# oscillator_board.net
KiCad netlist of a schematic drawn in EAGLE
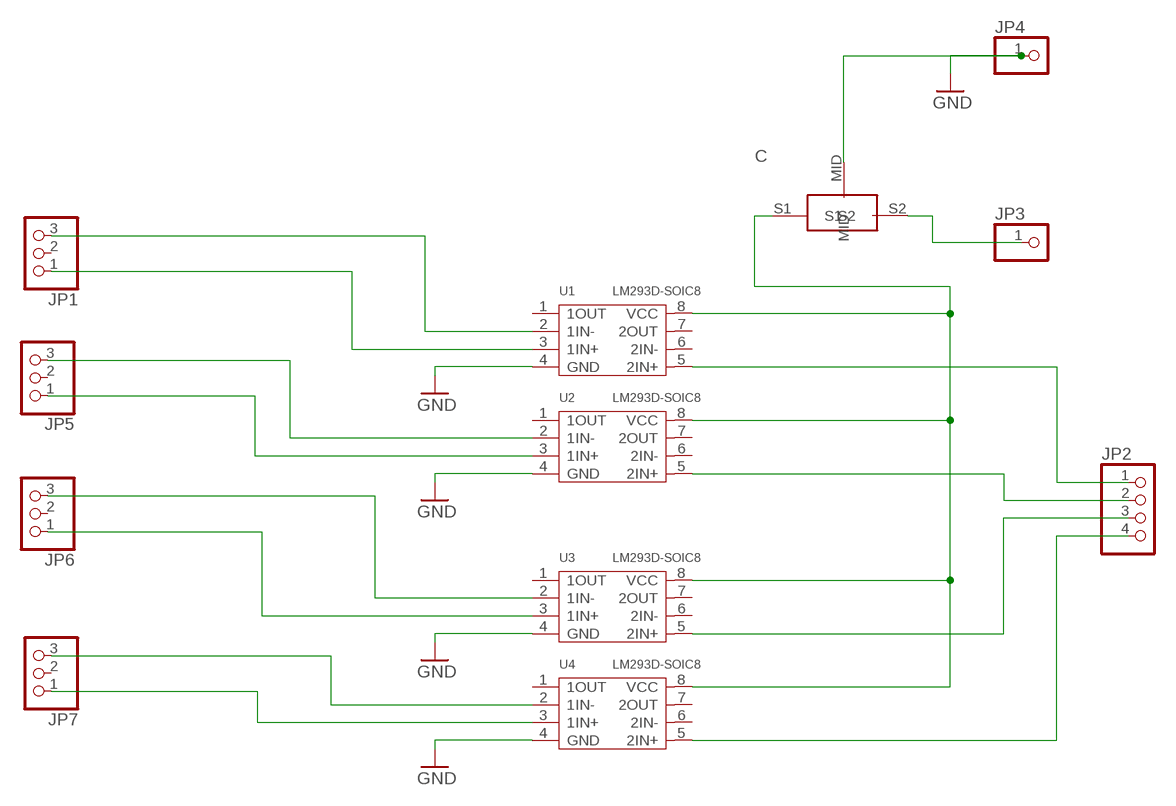
[diagram p0: schematic, sheet 1]

(export (version "E")
  (design (tool "Eeschema 10.0.6"))
  (components
    (comp (ref "JP1")
      (value "PINHD-1X3")
      (footprint "eagle-import:1X03")
      (libsource (lib "eagle-import") (part "PINHD-1X3"))
    )
    (comp (ref "JP2")
      (value "PINHD-1X4")
      (footprint "eagle-import:1X04")
      (libsource (lib "eagle-import") (part "PINHD-1X4"))
    )
    (comp (ref "JP3")
      (value "PINHD-1X1")
      (footprint "eagle-import:1X01")
      (libsource (lib "eagle-import") (part "PINHD-1X1"))
    )
    (comp (ref "JP4")
      (value "PINHD-1X1")
      (footprint "eagle-import:1X01")
      (libsource (lib "eagle-import") (part "PINHD-1X1"))
    )
    (comp (ref "JP5")
      (value "PINHD-1X3")
      (footprint "eagle-import:1X03")
      (libsource (lib "eagle-import") (part "PINHD-1X3"))
    )
    (comp (ref "JP6")
      (value "PINHD-1X3")
      (footprint "eagle-import:1X03")
      (libsource (lib "eagle-import") (part "PINHD-1X3"))
    )
    (comp (ref "JP7")
      (value "PINHD-1X3")
      (footprint "eagle-import:1X03")
      (libsource (lib "eagle-import") (part "PINHD-1X3"))
    )
    (comp (ref "OSCILLATOR1")
      (value "CSMD")
      (footprint "eagle-import:C")
      (libsource (lib "eagle-import") (part "CSMD"))
    )
    (comp (ref "U1")
      (value "LM293D-SOIC8")
      (footprint "eagle-import:SOIC8-1.27-5X4MM")
      (fields (field (name "MPN") "LM293D") (field (name "SPICEPREFIX") "X"))
      (libsource (lib "eagle-import") (part "AMPLIFIER-LM293D(SOIC8)"))
    )
    (comp (ref "U2")
      (value "LM293D-SOIC8")
      (footprint "eagle-import:SOIC8-1.27-5X4MM")
      (fields (field (name "MPN") "LM293D"))
      (libsource (lib "eagle-import") (part "AMPLIFIER-LM293D(SOIC8)"))
    )
    (comp (ref "U3")
      (value "LM293D-SOIC8")
      (footprint "eagle-import:SOIC8-1.27-5X4MM")
      (fields (field (name "MPN") "LM293D"))
      (libsource (lib "eagle-import") (part "AMPLIFIER-LM293D(SOIC8)"))
    )
    (comp (ref "U4")
      (value "LM293D-SOIC8")
      (footprint "eagle-import:SOIC8-1.27-5X4MM")
      (fields (field (name "MPN") "LM293D"))
      (libsource (lib "eagle-import") (part "AMPLIFIER-LM293D(SOIC8)"))
    )
  )
  (nets
    (net (code "1") (name "GND") (class "Default")
      (node (ref "JP4") (pin "1") (pinfunction "1_1") (pintype "passive"))
      (node (ref "OSCILLATOR1") (pin "MID") (pinfunction "MID_MID") (pintype "bidirectional"))
      (node (ref "U1") (pin "4") (pinfunction "GND_4") (pintype "power_in"))
      (node (ref "U2") (pin "4") (pinfunction "GND_4") (pintype "power_in"))
      (node (ref "U3") (pin "4") (pinfunction "GND_4") (pintype "power_in"))
      (node (ref "U4") (pin "4") (pinfunction "GND_4") (pintype "power_in"))
    )
    (net (code "2") (name "Net-(JP3-Pad1)") (class "Default")
      (node (ref "JP3") (pin "1") (pinfunction "1_1") (pintype "passive"))
      (node (ref "OSCILLATOR1") (pin "S2") (pinfunction "S2_S2") (pintype "bidirectional"))
    )
    (net (code "3") (name "Net-(U1-1IN+)") (class "Default")
      (node (ref "JP1") (pin "1") (pinfunction "1_1") (pintype "passive"))
      (node (ref "U1") (pin "3") (pinfunction "1IN+_3") (pintype "input"))
    )
    (net (code "4") (name "Net-(U1-1IN-)") (class "Default")
      (node (ref "JP1") (pin "3") (pinfunction "3_3") (pintype "passive"))
      (node (ref "U1") (pin "2") (pinfunction "1IN-_2") (pintype "input"))
    )
    (net (code "5") (name "Net-(U1-2IN+)") (class "Default")
      (node (ref "JP2") (pin "1") (pinfunction "1_1") (pintype "passive"))
      (node (ref "U1") (pin "5") (pinfunction "2IN+_5") (pintype "input"))
    )
    (net (code "6") (name "Net-(U1-VCC)") (class "Default")
      (node (ref "OSCILLATOR1") (pin "S1") (pinfunction "S1_S1") (pintype "bidirectional"))
      (node (ref "U1") (pin "8") (pinfunction "VCC_8") (pintype "power_in"))
      (node (ref "U2") (pin "8") (pinfunction "VCC_8") (pintype "power_in"))
      (node (ref "U3") (pin "8") (pinfunction "VCC_8") (pintype "power_in"))
      (node (ref "U4") (pin "8") (pinfunction "VCC_8") (pintype "power_in"))
    )
    (net (code "7") (name "Net-(U2-1IN+)") (class "Default")
      (node (ref "JP5") (pin "1") (pinfunction "1_1") (pintype "passive"))
      (node (ref "U2") (pin "3") (pinfunction "1IN+_3") (pintype "input"))
    )
    (net (code "8") (name "Net-(U2-1IN-)") (class "Default")
      (node (ref "JP5") (pin "3") (pinfunction "3_3") (pintype "passive"))
      (node (ref "U2") (pin "2") (pinfunction "1IN-_2") (pintype "input"))
    )
    (net (code "9") (name "Net-(U2-2IN+)") (class "Default")
      (node (ref "JP2") (pin "2") (pinfunction "2_2") (pintype "passive"))
      (node (ref "U2") (pin "5") (pinfunction "2IN+_5") (pintype "input"))
    )
    (net (code "10") (name "Net-(U3-1IN+)") (class "Default")
      (node (ref "JP6") (pin "1") (pinfunction "1_1") (pintype "passive"))
      (node (ref "U3") (pin "3") (pinfunction "1IN+_3") (pintype "input"))
    )
    (net (code "11") (name "Net-(U3-1IN-)") (class "Default")
      (node (ref "JP6") (pin "3") (pinfunction "3_3") (pintype "passive"))
      (node (ref "U3") (pin "2") (pinfunction "1IN-_2") (pintype "input"))
    )
    (net (code "12") (name "Net-(U3-2IN+)") (class "Default")
      (node (ref "JP2") (pin "3") (pinfunction "3_3") (pintype "passive"))
      (node (ref "U3") (pin "5") (pinfunction "2IN+_5") (pintype "input"))
    )
    (net (code "13") (name "Net-(U4-1IN+)") (class "Default")
      (node (ref "JP7") (pin "1") (pinfunction "1_1") (pintype "passive"))
      (node (ref "U4") (pin "3") (pinfunction "1IN+_3") (pintype "input"))
    )
    (net (code "14") (name "Net-(U4-1IN-)") (class "Default")
      (node (ref "JP7") (pin "3") (pinfunction "3_3") (pintype "passive"))
      (node (ref "U4") (pin "2") (pinfunction "1IN-_2") (pintype "input"))
    )
    (net (code "15") (name "Net-(U4-2IN+)") (class "Default")
      (node (ref "JP2") (pin "4") (pinfunction "4_4") (pintype "passive"))
      (node (ref "U4") (pin "5") (pinfunction "2IN+_5") (pintype "input"))
    )
    (net (code "16") (name "unconnected-(JP1-Pad2)") (class "Default")
      (node (ref "JP1") (pin "2") (pinfunction "2_2") (pintype "passive"))
    )
    (net (code "17") (name "unconnected-(JP5-Pad2)") (class "Default")
      (node (ref "JP5") (pin "2") (pinfunction "2_2") (pintype "passive"))
    )
    (net (code "18") (name "unconnected-(JP6-Pad2)") (class "Default")
      (node (ref "JP6") (pin "2") (pinfunction "2_2") (pintype "passive"))
    )
    (net (code "19") (name "unconnected-(JP7-Pad2)") (class "Default")
      (node (ref "JP7") (pin "2") (pinfunction "2_2") (pintype "passive"))
    )
    (net (code "20") (name "unconnected-(U1-1OUT-Pad1)") (class "Default")
      (node (ref "U1") (pin "1") (pinfunction "1OUT_1") (pintype "output"))
    )
    (net (code "21") (name "unconnected-(U1-2IN--Pad6)") (class "Default")
      (node (ref "U1") (pin "6") (pinfunction "2IN-_6") (pintype "input"))
    )
    (net (code "22") (name "unconnected-(U1-2OUT-Pad7)") (class "Default")
      (node (ref "U1") (pin "7") (pinfunction "2OUT_7") (pintype "output"))
    )
    (net (code "23") (name "unconnected-(U2-1OUT-Pad1)") (class "Default")
      (node (ref "U2") (pin "1") (pinfunction "1OUT_1") (pintype "output"))
    )
    (net (code "24") (name "unconnected-(U2-2IN--Pad6)") (class "Default")
      (node (ref "U2") (pin "6") (pinfunction "2IN-_6") (pintype "input"))
    )
    (net (code "25") (name "unconnected-(U2-2OUT-Pad7)") (class "Default")
      (node (ref "U2") (pin "7") (pinfunction "2OUT_7") (pintype "output"))
    )
    (net (code "26") (name "unconnected-(U3-1OUT-Pad1)") (class "Default")
      (node (ref "U3") (pin "1") (pinfunction "1OUT_1") (pintype "output"))
    )
    (net (code "27") (name "unconnected-(U3-2IN--Pad6)") (class "Default")
      (node (ref "U3") (pin "6") (pinfunction "2IN-_6") (pintype "input"))
    )
    (net (code "28") (name "unconnected-(U3-2OUT-Pad7)") (class "Default")
      (node (ref "U3") (pin "7") (pinfunction "2OUT_7") (pintype "output"))
    )
    (net (code "29") (name "unconnected-(U4-1OUT-Pad1)") (class "Default")
      (node (ref "U4") (pin "1") (pinfunction "1OUT_1") (pintype "output"))
    )
    (net (code "30") (name "unconnected-(U4-2IN--Pad6)") (class "Default")
      (node (ref "U4") (pin "6") (pinfunction "2IN-_6") (pintype "input"))
    )
    (net (code "31") (name "unconnected-(U4-2OUT-Pad7)") (class "Default")
      (node (ref "U4") (pin "7") (pinfunction "2OUT_7") (pintype "output"))
    )
  )
)
